# USB_To_Uart_5V_3V3_v1.net
KiCad netlist of a schematic drawn in EAGLE
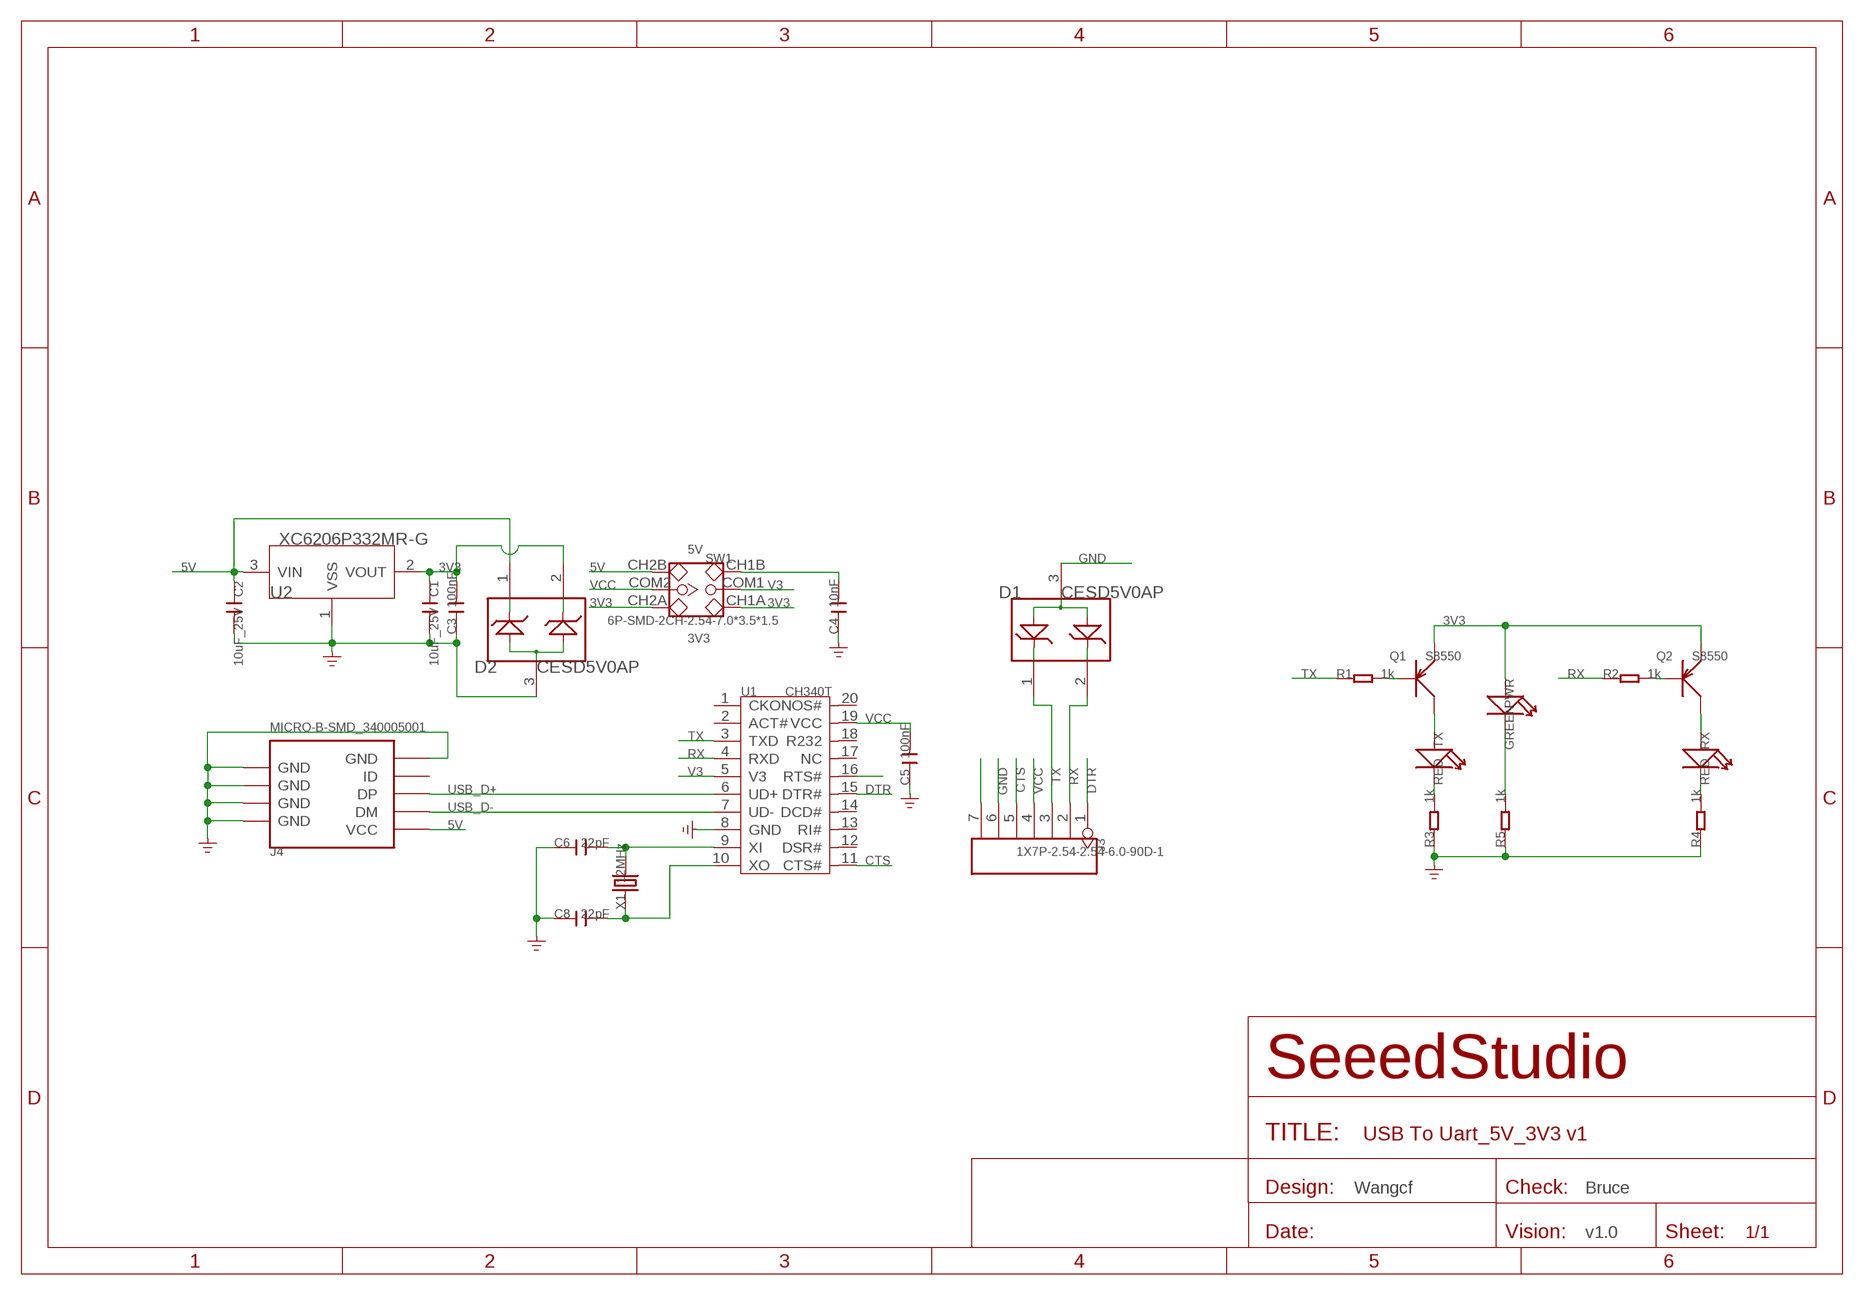
[diagram p0: schematic, sheet 1]

(export (version "E")
  (design (tool "Eeschema 10.0.6"))
  (components
    (comp (ref "C1")
      (value "10uF_25V")
      (footprint "eagle-import:C0805")
      (libsource (lib "eagle-import") (part "C-0805"))
    )
    (comp (ref "C2")
      (value "10uF_25V")
      (footprint "eagle-import:C0805")
      (libsource (lib "eagle-import") (part "C-0805"))
    )
    (comp (ref "C3")
      (value "100nF")
      (footprint "eagle-import:C0402")
      (libsource (lib "eagle-import") (part "C-0402"))
    )
    (comp (ref "C4")
      (value "10nF")
      (footprint "eagle-import:C0402")
      (libsource (lib "eagle-import") (part "C-0402"))
    )
    (comp (ref "C5")
      (value "100nF")
      (footprint "eagle-import:C0402")
      (libsource (lib "eagle-import") (part "C-0402"))
    )
    (comp (ref "C6")
      (value "22pF")
      (footprint "eagle-import:C0402")
      (libsource (lib "eagle-import") (part "C-0402"))
    )
    (comp (ref "C8")
      (value "22pF")
      (footprint "eagle-import:C0402")
      (libsource (lib "eagle-import") (part "C-0402"))
    )
    (comp (ref "D1")
      (value "CESD5V0AP")
      (footprint "eagle-import:SOT23")
      (libsource (lib "eagle-import") (part "D-ESD-3P"))
    )
    (comp (ref "D2")
      (value "CESD5V0AP")
      (footprint "eagle-import:SOT23")
      (libsource (lib "eagle-import") (part "D-ESD-3P"))
    )
    (comp (ref "J3")
      (value "1X7P-2.54-2.54-6.0-90D-1")
      (footprint "eagle-import:7P-2.54-65_35MIL")
      (libsource (lib "eagle-import") (part "HEADER-7P"))
    )
    (comp (ref "J4")
      (value "MICRO-B-SMD_340005001")
      (footprint "eagle-import:MICRO-USB")
      (libsource (lib "eagle-import") (part "USB-MINIUSB-5P-MICRO"))
    )
    (comp (ref "PWR")
      (value "GREEN")
      (footprint "eagle-import:LED-0603")
      (libsource (lib "eagle-import") (part "LED'0603'"))
    )
    (comp (ref "Q1")
      (value "S8550")
      (footprint "eagle-import:SOT23")
      (libsource (lib "eagle-import") (part "TRANSISTOR-PNP-SOT23"))
    )
    (comp (ref "Q2")
      (value "S8550")
      (footprint "eagle-import:SOT23")
      (libsource (lib "eagle-import") (part "TRANSISTOR-PNP-SOT23"))
    )
    (comp (ref "R1")
      (value "1k")
      (footprint "eagle-import:R0402")
      (libsource (lib "eagle-import") (part "R-0402"))
    )
    (comp (ref "R2")
      (value "1k")
      (footprint "eagle-import:R0402")
      (libsource (lib "eagle-import") (part "R-0402"))
    )
    (comp (ref "R3")
      (value "1k")
      (footprint "eagle-import:R0402")
      (libsource (lib "eagle-import") (part "R-0402"))
    )
    (comp (ref "R4")
      (value "1k")
      (footprint "eagle-import:R0402")
      (libsource (lib "eagle-import") (part "R-0402"))
    )
    (comp (ref "R5")
      (value "1k")
      (footprint "eagle-import:R0402")
      (libsource (lib "eagle-import") (part "R-0402"))
    )
    (comp (ref "RX")
      (value "RED")
      (footprint "eagle-import:LED-0603")
      (libsource (lib "eagle-import") (part "LED'0603'"))
    )
    (comp (ref "SW1")
      (value "6P-SMD-2CH-2.54-7.0*3.5*1.5")
      (footprint "eagle-import:6P-SMD-2CH-2.54-3.5X7.2")
      (libsource (lib "eagle-import") (part "SWITCH-2CH-6P-SMD"))
    )
    (comp (ref "TX")
      (value "RED")
      (footprint "eagle-import:LED-0603")
      (libsource (lib "eagle-import") (part "LED'0603'"))
    )
    (comp (ref "U1")
      (value "CH340T")
      (footprint "eagle-import:SSOP20")
      (libsource (lib "eagle-import") (part "CH340T"))
    )
    (comp (ref "U2")
      (value "XC6206P332MR-G")
      (footprint "eagle-import:SOT23")
      (libsource (lib "eagle-import") (part "XC6206MR"))
    )
    (comp (ref "X1")
      (value "12MHz")
      (footprint "eagle-import:2P-SMD-5X3.2")
      (libsource (lib "eagle-import") (part "CRYSTAL'5032'"))
    )
  )
  (nets
    (net (code "1") (name "/3V3") (class "Default")
      (node (ref "C1") (pin "1") (pinfunction "1_1") (pintype "passive"))
      (node (ref "C3") (pin "2") (pinfunction "2_2") (pintype "passive"))
      (node (ref "D2") (pin "2") (pinfunction "2_2") (pintype "bidirectional"))
      (node (ref "PWR") (pin "+") (pinfunction "+_+") (pintype "passive"))
      (node (ref "Q1") (pin "2") (pinfunction "E_2") (pintype "passive"))
      (node (ref "Q2") (pin "2") (pinfunction "E_2") (pintype "passive"))
      (node (ref "SW1") (pin "CH1A") (pinfunction "CH1A_CH1A") (pintype "bidirectional"))
      (node (ref "SW1") (pin "CH2A") (pinfunction "CH2A_CH2A") (pintype "bidirectional"))
      (node (ref "U2") (pin "2") (pinfunction "VOUT_2") (pintype "output"))
    )
    (net (code "2") (name "/5V") (class "Default")
      (node (ref "C2") (pin "1") (pinfunction "1_1") (pintype "passive"))
      (node (ref "D2") (pin "1") (pinfunction "1_1") (pintype "bidirectional"))
      (node (ref "J4") (pin "1") (pinfunction "VCC_1") (pintype "bidirectional"))
      (node (ref "SW1") (pin "CH2B") (pinfunction "CH2B_CH2B") (pintype "bidirectional"))
      (node (ref "U2") (pin "3") (pinfunction "VIN_3") (pintype "input"))
    )
    (net (code "3") (name "/CTS") (class "Default")
      (node (ref "J3") (pin "5") (pinfunction "5_5") (pintype "bidirectional"))
      (node (ref "U1") (pin "11") (pinfunction "CTS#_11") (pintype "input"))
    )
    (net (code "4") (name "/DTR") (class "Default")
      (node (ref "J3") (pin "1") (pinfunction "1_1") (pintype "bidirectional"))
      (node (ref "U1") (pin "15") (pinfunction "DTR#_15") (pintype "output"))
    )
    (net (code "5") (name "/N$3") (class "Default")
      (node (ref "J3") (pin "7") (pinfunction "7_7") (pintype "bidirectional"))
      (node (ref "U1") (pin "16") (pinfunction "RTS#_16") (pintype "output"))
    )
    (net (code "6") (name "/NOS#") (class "Default")
      (node (ref "U1") (pin "20") (pinfunction "NOS#_20") (pintype "power_in"))
    )
    (net (code "7") (name "/RX") (class "Default")
      (node (ref "D1") (pin "2") (pinfunction "2_2") (pintype "bidirectional"))
      (node (ref "J3") (pin "2") (pinfunction "2_2") (pintype "bidirectional"))
      (node (ref "R2") (pin "1") (pinfunction "1_1") (pintype "passive"))
      (node (ref "U1") (pin "4") (pinfunction "RXD_4") (pintype "input"))
    )
    (net (code "8") (name "/TX") (class "Default")
      (node (ref "D1") (pin "1") (pinfunction "1_1") (pintype "bidirectional"))
      (node (ref "J3") (pin "3") (pinfunction "3_3") (pintype "bidirectional"))
      (node (ref "R1") (pin "1") (pinfunction "1_1") (pintype "passive"))
      (node (ref "U1") (pin "3") (pinfunction "TXD_3") (pintype "output"))
    )
    (net (code "9") (name "/USB_D+") (class "Default")
      (node (ref "J4") (pin "3") (pinfunction "DP_3") (pintype "bidirectional"))
      (node (ref "U1") (pin "6") (pinfunction "UD+_6") (pintype "bidirectional"))
    )
    (net (code "10") (name "/USB_D-") (class "Default")
      (node (ref "J4") (pin "2") (pinfunction "DM_2") (pintype "bidirectional"))
      (node (ref "U1") (pin "7") (pinfunction "UD-_7") (pintype "bidirectional"))
    )
    (net (code "11") (name "/V3") (class "Default")
      (node (ref "SW1") (pin "COM1") (pinfunction "COM1_COM1") (pintype "bidirectional"))
      (node (ref "U1") (pin "5") (pinfunction "V3_5") (pintype "power_in"))
    )
    (net (code "12") (name "/VCC") (class "Default")
      (node (ref "C5") (pin "2") (pinfunction "2_2") (pintype "passive"))
      (node (ref "J3") (pin "4") (pinfunction "4_4") (pintype "bidirectional"))
      (node (ref "SW1") (pin "COM2") (pinfunction "COM2_COM2") (pintype "bidirectional"))
      (node (ref "U1") (pin "19") (pinfunction "VCC_19") (pintype "power_in"))
    )
    (net (code "13") (name "GND_POWER") (class "Default")
      (node (ref "C1") (pin "2") (pinfunction "2_2") (pintype "passive"))
      (node (ref "C2") (pin "2") (pinfunction "2_2") (pintype "passive"))
      (node (ref "C3") (pin "1") (pinfunction "1_1") (pintype "passive"))
      (node (ref "C4") (pin "1") (pinfunction "1_1") (pintype "passive"))
      (node (ref "C5") (pin "1") (pinfunction "1_1") (pintype "passive"))
      (node (ref "C6") (pin "1") (pinfunction "1_1") (pintype "passive"))
      (node (ref "C8") (pin "1") (pinfunction "1_1") (pintype "passive"))
      (node (ref "D1") (pin "3") (pinfunction "3_3") (pintype "bidirectional"))
      (node (ref "D2") (pin "3") (pinfunction "3_3") (pintype "bidirectional"))
      (node (ref "J3") (pin "6") (pinfunction "6_6") (pintype "bidirectional"))
      (node (ref "J4") (pin "5") (pinfunction "GND_5") (pintype "bidirectional"))
      (node (ref "J4") (pin "S1") (pinfunction "GND_S1") (pintype "bidirectional"))
      (node (ref "J4") (pin "S2") (pinfunction "GND_S2") (pintype "bidirectional"))
      (node (ref "J4") (pin "S3") (pinfunction "GND_S3") (pintype "bidirectional"))
      (node (ref "J4") (pin "S4") (pinfunction "GND_S4") (pintype "bidirectional"))
      (node (ref "J4") (pin "S5") (pinfunction "GND_S5") (pintype "bidirectional"))
      (node (ref "J4") (pin "S6") (pinfunction "GND_S6") (pintype "bidirectional"))
      (node (ref "R3") (pin "1") (pinfunction "1_1") (pintype "passive"))
      (node (ref "R4") (pin "1") (pinfunction "1_1") (pintype "passive"))
      (node (ref "R5") (pin "1") (pinfunction "1_1") (pintype "passive"))
      (node (ref "U1") (pin "8") (pinfunction "GND_8") (pintype "power_in"))
      (node (ref "U2") (pin "1") (pinfunction "VSS_1") (pintype "power_in"))
    )
    (net (code "14") (name "Net-(C4-Pad2)") (class "Default")
      (node (ref "C4") (pin "2") (pinfunction "2_2") (pintype "passive"))
      (node (ref "SW1") (pin "CH1B") (pinfunction "CH1B_CH1B") (pintype "bidirectional"))
    )
    (net (code "15") (name "Net-(PWR-Pad-)") (class "Default")
      (node (ref "PWR") (pin "-") (pinfunction "-_-") (pintype "passive"))
      (node (ref "R5") (pin "2") (pinfunction "2_2") (pintype "passive"))
    )
    (net (code "16") (name "Net-(Q1-B)") (class "Default")
      (node (ref "Q1") (pin "1") (pinfunction "B_1") (pintype "passive"))
      (node (ref "R1") (pin "2") (pinfunction "2_2") (pintype "passive"))
    )
    (net (code "17") (name "Net-(Q1-C)") (class "Default")
      (node (ref "Q1") (pin "3") (pinfunction "C_3") (pintype "passive"))
      (node (ref "TX") (pin "+") (pinfunction "+_+") (pintype "passive"))
    )
    (net (code "18") (name "Net-(Q2-B)") (class "Default")
      (node (ref "Q2") (pin "1") (pinfunction "B_1") (pintype "passive"))
      (node (ref "R2") (pin "2") (pinfunction "2_2") (pintype "passive"))
    )
    (net (code "19") (name "Net-(Q2-C)") (class "Default")
      (node (ref "Q2") (pin "3") (pinfunction "C_3") (pintype "passive"))
      (node (ref "RX") (pin "+") (pinfunction "+_+") (pintype "passive"))
    )
    (net (code "20") (name "Net-(R3-Pad2)") (class "Default")
      (node (ref "R3") (pin "2") (pinfunction "2_2") (pintype "passive"))
      (node (ref "TX") (pin "-") (pinfunction "-_-") (pintype "passive"))
    )
    (net (code "21") (name "Net-(R4-Pad2)") (class "Default")
      (node (ref "R4") (pin "2") (pinfunction "2_2") (pintype "passive"))
      (node (ref "RX") (pin "-") (pinfunction "-_-") (pintype "passive"))
    )
    (net (code "22") (name "Net-(U1-XI)") (class "Default")
      (node (ref "C6") (pin "2") (pinfunction "2_2") (pintype "passive"))
      (node (ref "U1") (pin "9") (pinfunction "XI_9") (pintype "input"))
      (node (ref "X1") (pin "2") (pinfunction "2_2") (pintype "passive"))
    )
    (net (code "23") (name "Net-(U1-XO)") (class "Default")
      (node (ref "C8") (pin "2") (pinfunction "2_2") (pintype "passive"))
      (node (ref "U1") (pin "10") (pinfunction "XO_10") (pintype "output"))
      (node (ref "X1") (pin "1") (pinfunction "1_1") (pintype "passive"))
    )
    (net (code "24") (name "unconnected-(J4-ID-Pad4)") (class "Default")
      (node (ref "J4") (pin "4") (pinfunction "ID_4") (pintype "bidirectional"))
    )
    (net (code "25") (name "unconnected-(U1-ACT#-Pad2)") (class "Default")
      (node (ref "U1") (pin "2") (pinfunction "ACT#_2") (pintype "output"))
    )
    (net (code "26") (name "unconnected-(U1-CKO-Pad1)") (class "Default")
      (node (ref "U1") (pin "1") (pinfunction "CKO_1") (pintype "output"))
    )
    (net (code "27") (name "unconnected-(U1-DCD#-Pad14)") (class "Default")
      (node (ref "U1") (pin "14") (pinfunction "DCD#_14") (pintype "input"))
    )
    (net (code "28") (name "unconnected-(U1-DSR#-Pad12)") (class "Default")
      (node (ref "U1") (pin "12") (pinfunction "DSR#_12") (pintype "input"))
    )
    (net (code "29") (name "unconnected-(U1-NC-Pad17)") (class "Default")
      (node (ref "U1") (pin "17") (pinfunction "NC_17") (pintype "no_connect"))
    )
    (net (code "30") (name "unconnected-(U1-R232-Pad18)") (class "Default")
      (node (ref "U1") (pin "18") (pinfunction "R232_18") (pintype "input"))
    )
    (net (code "31") (name "unconnected-(U1-RI#-Pad13)") (class "Default")
      (node (ref "U1") (pin "13") (pinfunction "RI#_13") (pintype "input"))
    )
  )
)
